# main.net
KiCad netlist of a schematic drawn in Altium Designer
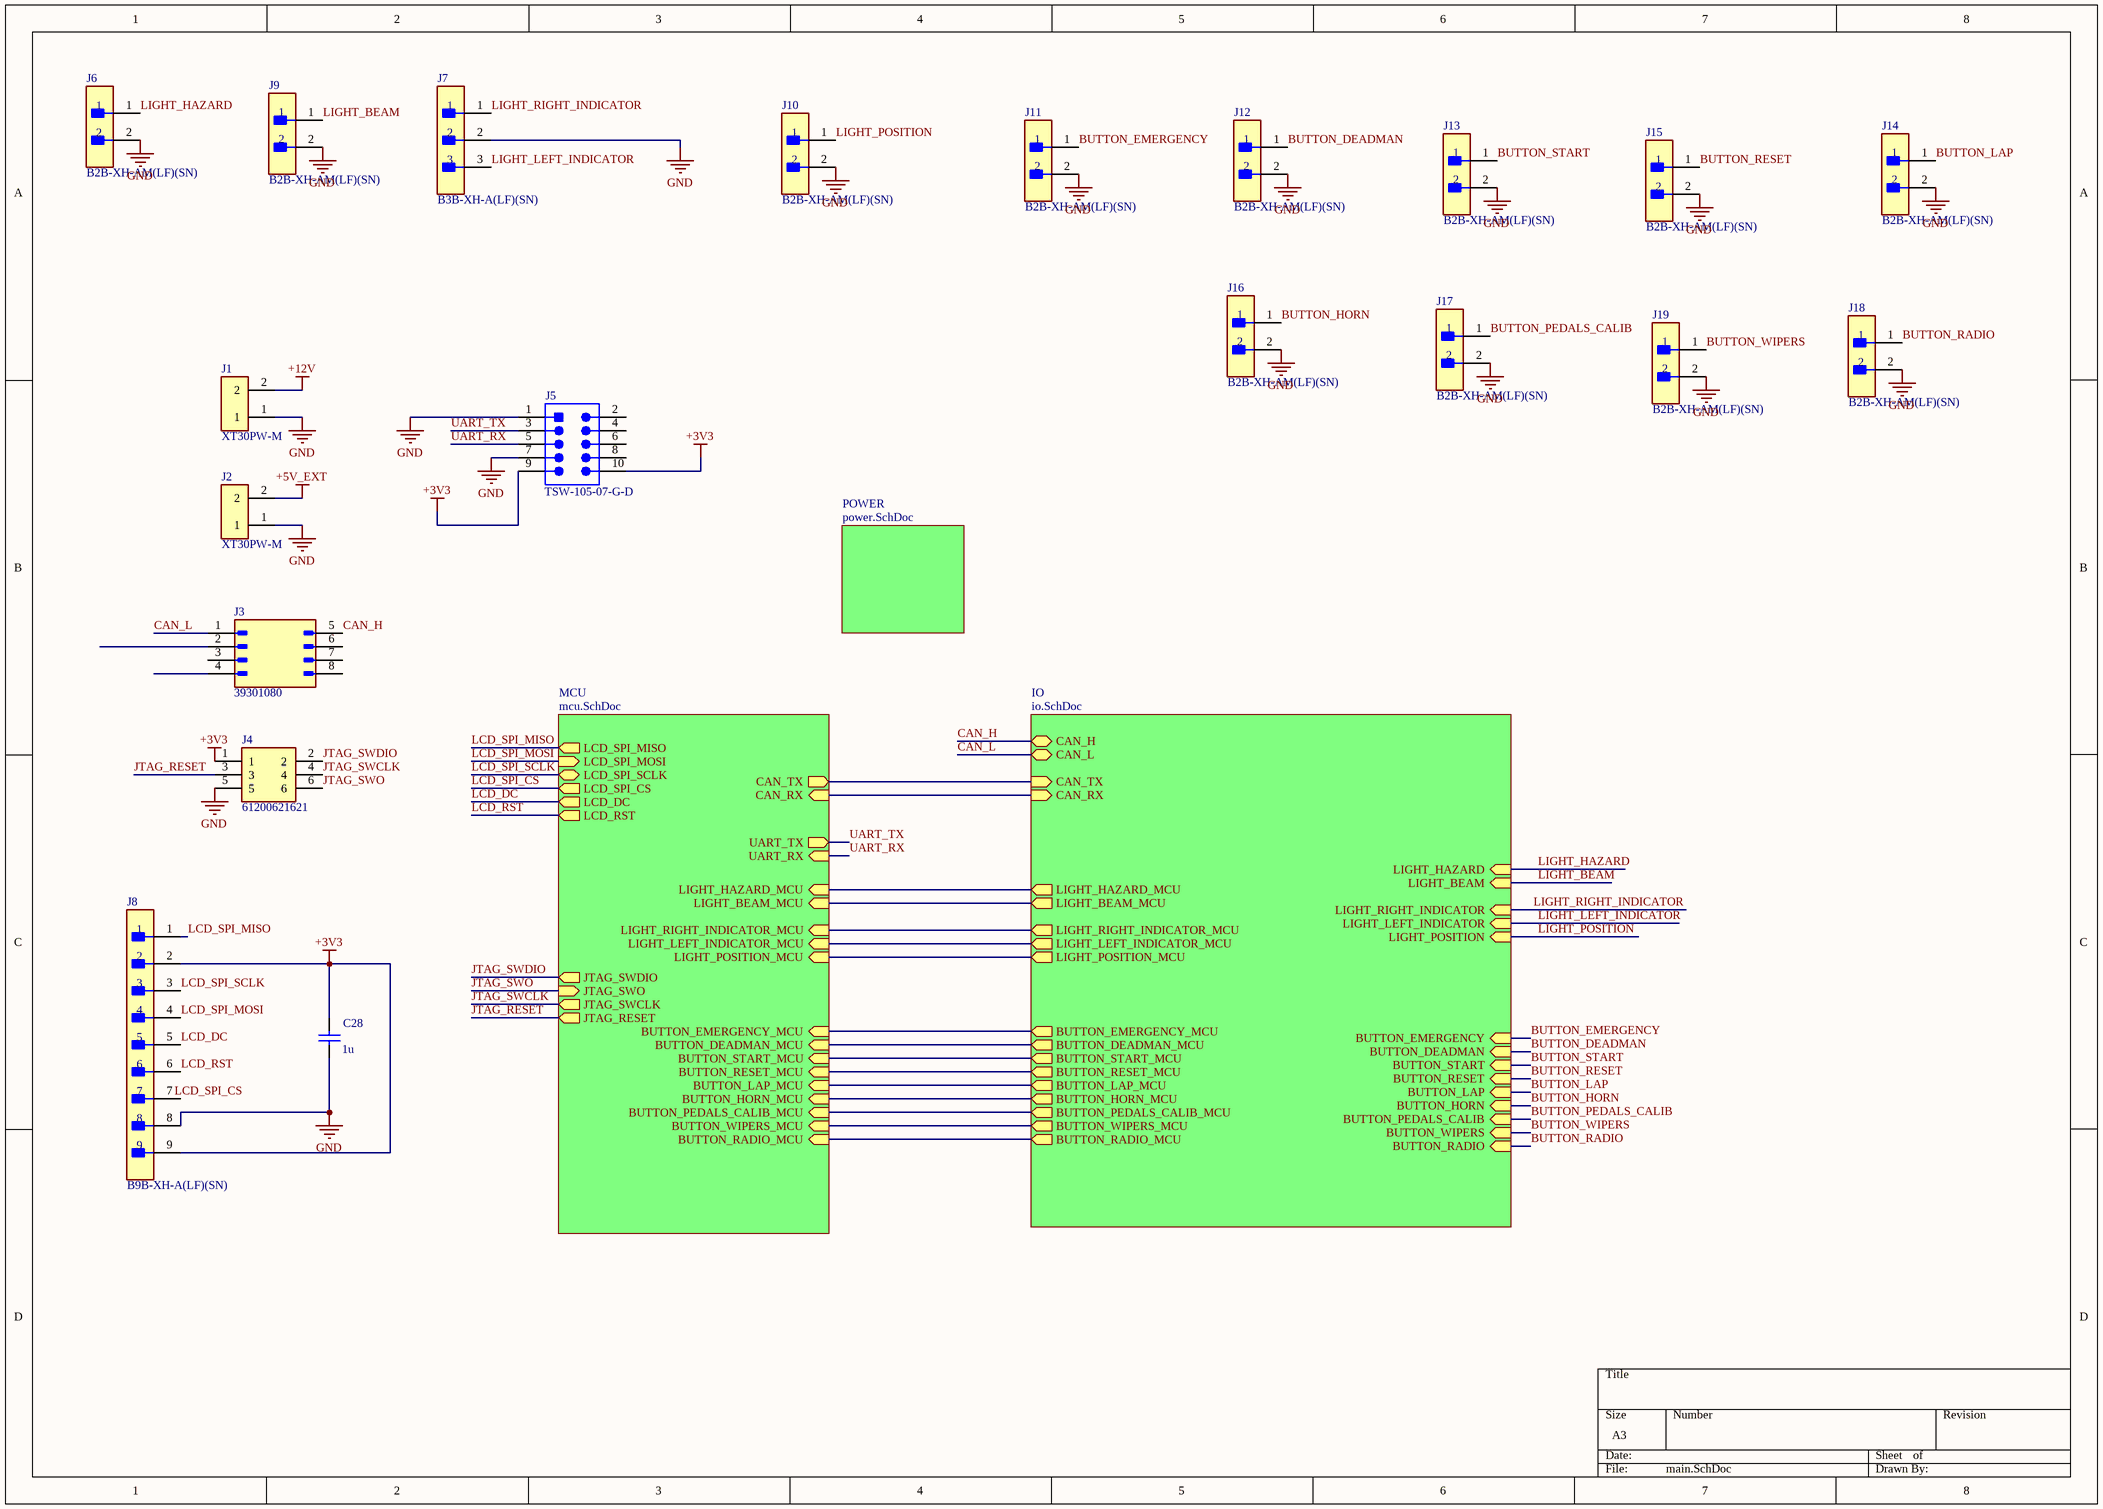
[diagram p0: main.SchDoc]

(export (version "E")
  (design (tool "Eeschema 10.0.6"))
  (components
    (comp (ref "C28")
      (value "1u")
      (footprint "CAPC1206(3216)150_L")
      (description "CAP 1.8uF 10V ±5% 1206 (3216 Metric) Thickness 1.45mm SMD")
      (fields (field (name "TOLERANCE") "Â±5%"))
      (libsource (lib "Altium Content Vault") (part "CAP"))
    )
    (comp (ref "J1")
      (value "XT30PW-M")
      (footprint "XT30PWM")
      (description "Plug; XT30; Male; 30A; Low Temperature Rise Fire Retardant")
      (libsource (lib "HydrogreenLibrary") (part "XT30PW-M"))
    )
    (comp (ref "J2")
      (value "XT30PW-M")
      (footprint "XT30PWM")
      (description "Plug; XT30; Male; 30A; Low Temperature Rise Fire Retardant")
      (libsource (lib "HydrogreenLibrary") (part "XT30PW-M"))
    )
    (comp (ref "J3")
      (value "39301080")
      (footprint "39301080")
      (description "Connector Wire to Board Header 8 Position 4.2mm Solder Right Angle Thru-Hole Tray")
      (fields (field (name "MF") "Molex") (field (name "MP") "39-30-1080"))
      (libsource (lib "HydrogreenLibrary") (part "39301080"))
    )
    (comp (ref "J4")
      (value "61200621621")
      (footprint "61200621621")
      (description "Conn Shrouded Header (4 Sides) M 6 POS 2.54mm Solder ST Top Entry Thru-Hole Tray")
      (fields
        (field (name "MOUSER PART NUMBER") "710-61200621621")
        (field (name "MANUFACTURER") "Wurth Elektronik")
      )
      (libsource (lib "HydrogreenLibrary") (part "61200621621"))
    )
    (comp (ref "J5")
      (value "TSW-105-07-G-D")
      (footprint "SMTC-TSW-105-07-G-D_V")
      (fields (field (name "MANUFACTURER") "Samtec-Inc."))
      (libsource (lib "Altium Content Vault") (part "CN-2P-M-R10"))
    )
    (comp (ref "J6")
      (value "B2B-XH-AM(LF)(SN)")
      (footprint "FP-B2B-XH-AM_LF_SN-MFG")
      (description "CONN HEADER VERT 2POS 2.5MM")
      (libsource (lib "Altium Content Vault") (part "3bc925449376181038e59eaffc5286c"))
    )
    (comp (ref "J7")
      (value "B3B-XH-A(LF)(SN)")
      (footprint "FP-B3B-XH-A_LF_SN-MFG")
      (description "CONN HEADER VERT 3POS 2.5MM")
      (libsource (lib "Altium Content Vault") (part "0d3f023dd272f625e17a2be33dea85f"))
    )
    (comp (ref "J8")
      (value "B9B-XH-A(LF)(SN)")
      (footprint "FP-B9B-XH-A_LF_SN-MFG")
      (description "CONN HEADER VERT 9POS 2.5MM")
      (libsource (lib "Altium Content Vault") (part "dac6df820644cf490af5575b4ac23d9"))
    )
    (comp (ref "J9")
      (value "B2B-XH-AM(LF)(SN)")
      (footprint "FP-B2B-XH-AM_LF_SN-MFG")
      (description "CONN HEADER VERT 2POS 2.5MM")
      (libsource (lib "Altium Content Vault") (part "3bc925449376181038e59eaffc5286c"))
    )
    (comp (ref "J10")
      (value "B2B-XH-AM(LF)(SN)")
      (footprint "FP-B2B-XH-AM_LF_SN-MFG")
      (description "CONN HEADER VERT 2POS 2.5MM")
      (libsource (lib "Altium Content Vault") (part "3bc925449376181038e59eaffc5286c"))
    )
    (comp (ref "J11")
      (value "B2B-XH-AM(LF)(SN)")
      (footprint "FP-B2B-XH-AM_LF_SN-MFG")
      (description "CONN HEADER VERT 2POS 2.5MM")
      (libsource (lib "Altium Content Vault") (part "3bc925449376181038e59eaffc5286c"))
    )
    (comp (ref "J12")
      (value "B2B-XH-AM(LF)(SN)")
      (footprint "FP-B2B-XH-AM_LF_SN-MFG")
      (description "CONN HEADER VERT 2POS 2.5MM")
      (libsource (lib "Altium Content Vault") (part "3bc925449376181038e59eaffc5286c"))
    )
    (comp (ref "J13")
      (value "B2B-XH-AM(LF)(SN)")
      (footprint "FP-B2B-XH-AM_LF_SN-MFG")
      (description "CONN HEADER VERT 2POS 2.5MM")
      (libsource (lib "Altium Content Vault") (part "3bc925449376181038e59eaffc5286c"))
    )
    (comp (ref "J14")
      (value "B2B-XH-AM(LF)(SN)")
      (footprint "FP-B2B-XH-AM_LF_SN-MFG")
      (description "CONN HEADER VERT 2POS 2.5MM")
      (libsource (lib "Altium Content Vault") (part "3bc925449376181038e59eaffc5286c"))
    )
    (comp (ref "J15")
      (value "B2B-XH-AM(LF)(SN)")
      (footprint "FP-B2B-XH-AM_LF_SN-MFG")
      (description "CONN HEADER VERT 2POS 2.5MM")
      (libsource (lib "Altium Content Vault") (part "3bc925449376181038e59eaffc5286c"))
    )
    (comp (ref "J16")
      (value "B2B-XH-AM(LF)(SN)")
      (footprint "FP-B2B-XH-AM_LF_SN-MFG")
      (description "CONN HEADER VERT 2POS 2.5MM")
      (libsource (lib "Altium Content Vault") (part "3bc925449376181038e59eaffc5286c"))
    )
    (comp (ref "J17")
      (value "B2B-XH-AM(LF)(SN)")
      (footprint "FP-B2B-XH-AM_LF_SN-MFG")
      (description "CONN HEADER VERT 2POS 2.5MM")
      (libsource (lib "Altium Content Vault") (part "3bc925449376181038e59eaffc5286c"))
    )
    (comp (ref "J18")
      (value "B2B-XH-AM(LF)(SN)")
      (footprint "FP-B2B-XH-AM_LF_SN-MFG")
      (description "CONN HEADER VERT 2POS 2.5MM")
      (libsource (lib "Altium Content Vault") (part "3bc925449376181038e59eaffc5286c"))
    )
    (comp (ref "J19")
      (value "B2B-XH-AM(LF)(SN)")
      (footprint "FP-B2B-XH-AM_LF_SN-MFG")
      (description "CONN HEADER VERT 2POS 2.5MM")
      (libsource (lib "Altium Content Vault") (part "3bc925449376181038e59eaffc5286c"))
    )
  )
  (nets
    (net (code "1") (name "+3V3") (class "Default")
      (node (ref "C28") (pin "1") (pinfunction "1_1") (pintype "passive"))
      (node (ref "J4") (pin "1") (pinfunction "1_1") (pintype "passive"))
      (node (ref "J5") (pin "10") (pinfunction "10_10") (pintype "passive"))
      (node (ref "J5") (pin "9") (pinfunction "9_9") (pintype "passive"))
      (node (ref "J8") (pin "2") (pinfunction "2_2") (pintype "passive"))
      (node (ref "J8") (pin "9") (pinfunction "9_9") (pintype "passive"))
    )
    (net (code "2") (name "+5V_EXT") (class "Default")
      (node (ref "J2") (pin "2") (pinfunction "2_2") (pintype "passive"))
    )
    (net (code "3") (name "+12V") (class "Default")
      (node (ref "J1") (pin "2") (pinfunction "2_2") (pintype "passive"))
    )
    (net (code "4") (name "/BUTTON_DEADMAN") (class "Default")
      (node (ref "J12") (pin "1") (pinfunction "1_1") (pintype "passive"))
    )
    (net (code "6") (name "/BUTTON_EMERGENCY") (class "Default")
      (node (ref "J11") (pin "1") (pinfunction "1_1") (pintype "passive"))
    )
    (net (code "8") (name "/BUTTON_HORN") (class "Default")
      (node (ref "J16") (pin "1") (pinfunction "1_1") (pintype "passive"))
    )
    (net (code "10") (name "/BUTTON_LAP") (class "Default")
      (node (ref "J14") (pin "1") (pinfunction "1_1") (pintype "passive"))
    )
    (net (code "12") (name "/BUTTON_PEDALS_CALIB") (class "Default")
      (node (ref "J17") (pin "1") (pinfunction "1_1") (pintype "passive"))
    )
    (net (code "14") (name "/BUTTON_RADIO") (class "Default")
      (node (ref "J18") (pin "1") (pinfunction "1_1") (pintype "passive"))
    )
    (net (code "16") (name "/BUTTON_RESET") (class "Default")
      (node (ref "J15") (pin "1") (pinfunction "1_1") (pintype "passive"))
    )
    (net (code "18") (name "/BUTTON_START") (class "Default")
      (node (ref "J13") (pin "1") (pinfunction "1_1") (pintype "passive"))
    )
    (net (code "20") (name "/BUTTON_WIPERS") (class "Default")
      (node (ref "J19") (pin "1") (pinfunction "1_1") (pintype "passive"))
    )
    (net (code "22") (name "/CAN_H") (class "Default") (node (ref "J3") (pin "5") (pintype "passive")))
    (net (code "23") (name "/CAN_L") (class "Default") (node (ref "J3") (pin "1") (pintype "passive")))
    (net (code "26") (name "/JTAG_RESET") (class "Default")
      (node (ref "J4") (pin "3") (pinfunction "3_3") (pintype "passive"))
    )
    (net (code "27") (name "/JTAG_SWCLK") (class "Default")
      (node (ref "J4") (pin "4") (pinfunction "4_4") (pintype "passive"))
    )
    (net (code "28") (name "/JTAG_SWDIO") (class "Default")
      (node (ref "J4") (pin "2") (pinfunction "2_2") (pintype "passive"))
    )
    (net (code "29") (name "/JTAG_SWO") (class "Default")
      (node (ref "J4") (pin "6") (pinfunction "6_6") (pintype "passive"))
    )
    (net (code "30") (name "/LCD_DC") (class "Default")
      (node (ref "J8") (pin "5") (pinfunction "5_5") (pintype "passive"))
    )
    (net (code "31") (name "/LCD_RST") (class "Default")
      (node (ref "J8") (pin "6") (pinfunction "6_6") (pintype "passive"))
    )
    (net (code "33") (name "/LCD_SPI_MISO") (class "Default")
      (node (ref "J8") (pin "1") (pinfunction "1_1") (pintype "passive"))
    )
    (net (code "34") (name "/LCD_SPI_MOSI") (class "Default")
      (node (ref "J8") (pin "4") (pinfunction "4_4") (pintype "passive"))
    )
    (net (code "35") (name "/LCD_SPI_SCLK") (class "Default")
      (node (ref "J8") (pin "3") (pinfunction "3_3") (pintype "passive"))
    )
    (net (code "36") (name "/LIGHT_BEAM") (class "Default")
      (node (ref "J9") (pin "1") (pinfunction "1_1") (pintype "passive"))
    )
    (net (code "38") (name "/LIGHT_HAZARD") (class "Default")
      (node (ref "J6") (pin "1") (pinfunction "1_1") (pintype "passive"))
    )
    (net (code "40") (name "/LIGHT_LEFT_INDICATOR") (class "Default")
      (node (ref "J7") (pin "3") (pinfunction "3_3") (pintype "passive"))
    )
    (net (code "42") (name "/LIGHT_POSITION") (class "Default")
      (node (ref "J10") (pin "1") (pinfunction "1_1") (pintype "passive"))
    )
    (net (code "44") (name "/LIGHT_RIGHT_INDICATOR") (class "Default")
      (node (ref "J7") (pin "1") (pinfunction "1_1") (pintype "passive"))
    )
    (net (code "46") (name "/UART_RX") (class "Default")
      (node (ref "J5") (pin "5") (pinfunction "5_5") (pintype "passive"))
    )
    (net (code "47") (name "/UART_TX") (class "Default")
      (node (ref "J5") (pin "3") (pinfunction "3_3") (pintype "passive"))
    )
    (net (code "48") (name "GND") (class "Default")
      (node (ref "C28") (pin "2") (pinfunction "2_2") (pintype "passive"))
      (node (ref "J1") (pin "1") (pinfunction "1_1") (pintype "passive"))
      (node (ref "J10") (pin "2") (pinfunction "2_2") (pintype "passive"))
      (node (ref "J11") (pin "2") (pinfunction "2_2") (pintype "passive"))
      (node (ref "J12") (pin "2") (pinfunction "2_2") (pintype "passive"))
      (node (ref "J13") (pin "2") (pinfunction "2_2") (pintype "passive"))
      (node (ref "J14") (pin "2") (pinfunction "2_2") (pintype "passive"))
      (node (ref "J15") (pin "2") (pinfunction "2_2") (pintype "passive"))
      (node (ref "J16") (pin "2") (pinfunction "2_2") (pintype "passive"))
      (node (ref "J17") (pin "2") (pinfunction "2_2") (pintype "passive"))
      (node (ref "J18") (pin "2") (pinfunction "2_2") (pintype "passive"))
      (node (ref "J19") (pin "2") (pinfunction "2_2") (pintype "passive"))
      (node (ref "J2") (pin "1") (pinfunction "1_1") (pintype "passive"))
      (node (ref "J4") (pin "5") (pinfunction "5_5") (pintype "passive"))
      (node (ref "J5") (pin "1") (pinfunction "1_1") (pintype "passive"))
      (node (ref "J5") (pin "7") (pinfunction "7_7") (pintype "passive"))
      (node (ref "J6") (pin "2") (pinfunction "2_2") (pintype "passive"))
      (node (ref "J7") (pin "2") (pinfunction "2_2") (pintype "passive"))
      (node (ref "J8") (pin "8") (pinfunction "8_8") (pintype "passive"))
      (node (ref "J9") (pin "2") (pinfunction "2_2") (pintype "passive"))
    )
    (net (code "49") (name "unconnected-(J3-Pad2)") (class "Default")
      (node (ref "J3") (pin "2") (pintype "passive"))
    )
    (net (code "50") (name "unconnected-(J3-Pad3)") (class "Default")
      (node (ref "J3") (pin "3") (pintype "passive"))
    )
    (net (code "51") (name "unconnected-(J3-Pad4)") (class "Default")
      (node (ref "J3") (pin "4") (pintype "passive"))
    )
    (net (code "52") (name "unconnected-(J3-Pad6)") (class "Default")
      (node (ref "J3") (pin "6") (pintype "passive"))
    )
    (net (code "53") (name "unconnected-(J3-Pad7)") (class "Default")
      (node (ref "J3") (pin "7") (pintype "passive"))
    )
    (net (code "54") (name "unconnected-(J3-Pad8)") (class "Default")
      (node (ref "J3") (pin "8") (pintype "passive"))
    )
    (net (code "55") (name "unconnected-(J5-Pad2)") (class "Default")
      (node (ref "J5") (pin "2") (pinfunction "2_2") (pintype "passive"))
    )
    (net (code "56") (name "unconnected-(J5-Pad4)") (class "Default")
      (node (ref "J5") (pin "4") (pinfunction "4_4") (pintype "passive"))
    )
    (net (code "57") (name "unconnected-(J5-Pad6)") (class "Default")
      (node (ref "J5") (pin "6") (pinfunction "6_6") (pintype "passive"))
    )
    (net (code "58") (name "unconnected-(J5-Pad8)") (class "Default")
      (node (ref "J5") (pin "8") (pinfunction "8_8") (pintype "passive"))
    )
    (net (code "59") (name "unconnected-(J8-Pad7)") (class "Default")
      (node (ref "J8") (pin "7") (pinfunction "7_7") (pintype "passive"))
    )
  )
)
